# -Linux.net
KiCad netlist of a schematic drawn in Altium Designer
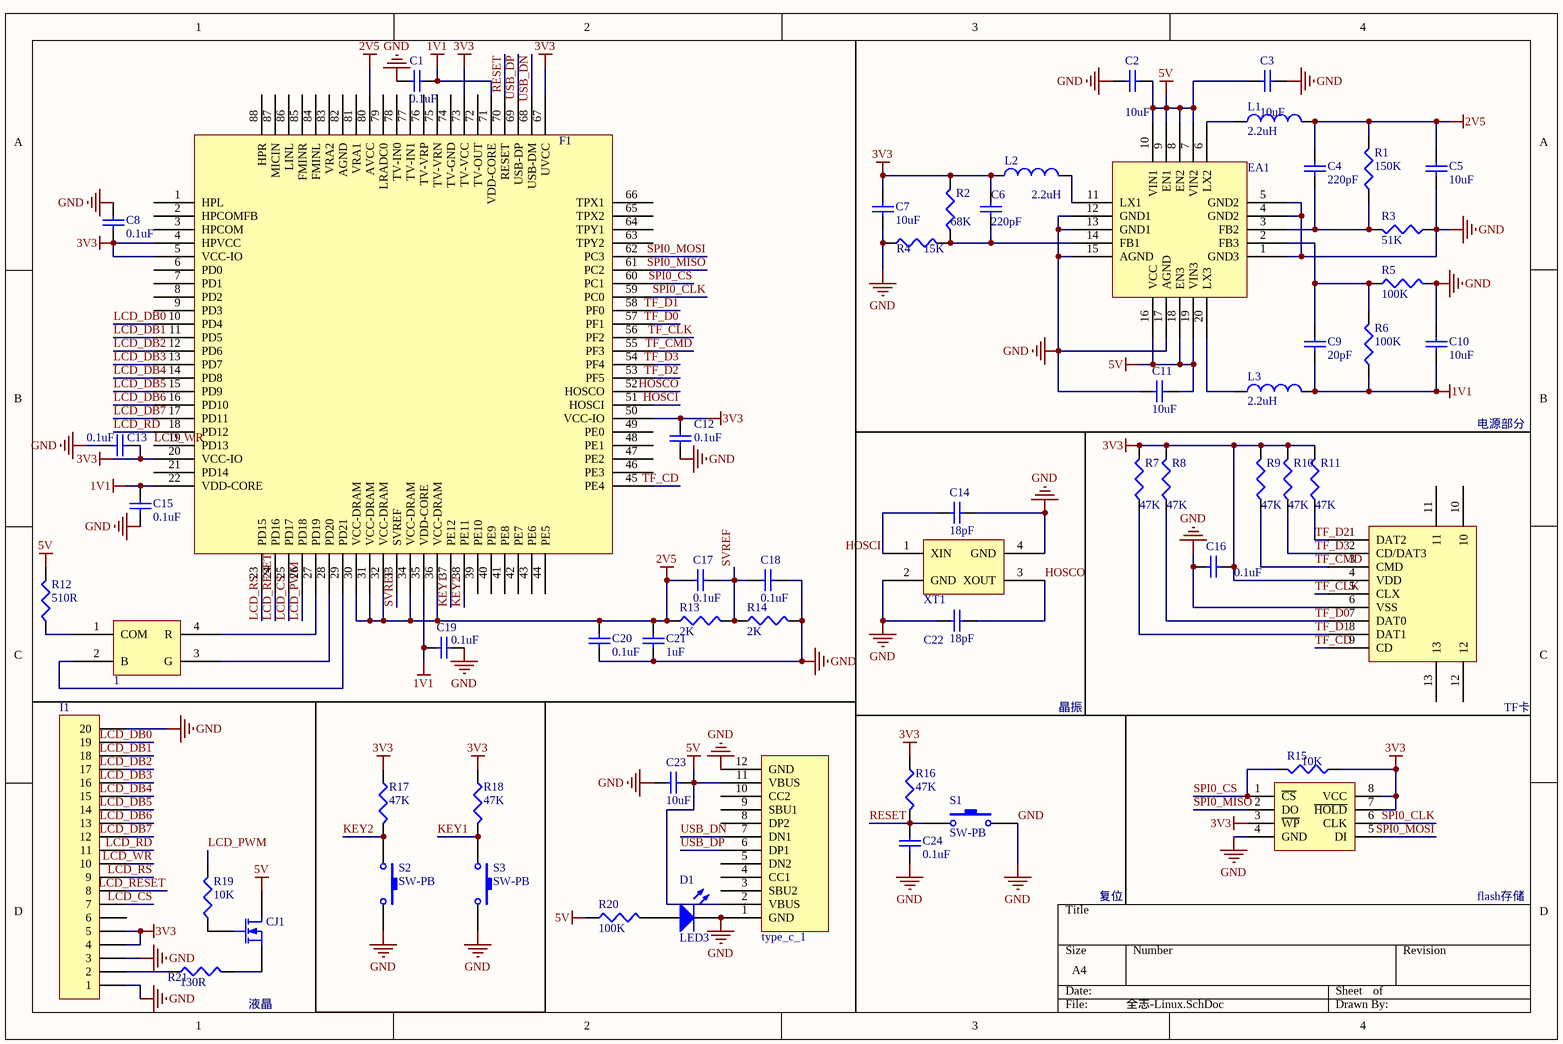
[diagram p0: 全志-Linux.SchDoc]

(export (version "E")
  (design (tool "Eeschema 10.0.6"))
  (components
    (comp (ref "*1") (value "tf卡") (footprint "tf卡座") (libsource (lib "schray_lib") (part "tf卡")))
    (comp (ref "1") (value "1615RGB") (footprint "1615RGB") (libsource (lib "schray_lib") (part "1615RGB")))
    (comp (ref "C1")
      (value "0.1uF")
      (footprint "C0402")
      (description "Capacitor (Semiconductor SIM Model)")
      (fields (field (name "Comment") "Cap Semi") (field (name "PUBLISHER") "Altium Limited"))
      (libsource (lib "Miscellaneous Devices") (part "Cap Semi"))
    )
    (comp (ref "C2")
      (value "10uF")
      (footprint "C0603")
      (description "Capacitor (Semiconductor SIM Model)")
      (fields (field (name "Comment") "Cap Semi") (field (name "PUBLISHER") "Altium Limited"))
      (libsource (lib "Miscellaneous Devices") (part "Cap Semi"))
    )
    (comp (ref "C3")
      (value "10uF")
      (footprint "C0603")
      (description "Capacitor (Semiconductor SIM Model)")
      (fields (field (name "Comment") "Cap Semi") (field (name "PUBLISHER") "Altium Limited"))
      (libsource (lib "Miscellaneous Devices") (part "Cap Semi"))
    )
    (comp (ref "C4")
      (value "220pF")
      (footprint "C0402")
      (description "Capacitor (Semiconductor SIM Model)")
      (fields (field (name "Comment") "Cap Semi") (field (name "PUBLISHER") "Altium Limited"))
      (libsource (lib "Miscellaneous Devices") (part "Cap Semi"))
    )
    (comp (ref "C5")
      (value "10uF")
      (footprint "C0603")
      (description "Capacitor (Semiconductor SIM Model)")
      (fields (field (name "Comment") "Cap Semi") (field (name "PUBLISHER") "Altium Limited"))
      (libsource (lib "Miscellaneous Devices") (part "Cap Semi"))
    )
    (comp (ref "C6")
      (value "220pF")
      (footprint "C0402")
      (description "Capacitor (Semiconductor SIM Model)")
      (fields (field (name "Comment") "Cap Semi") (field (name "PUBLISHER") "Altium Limited"))
      (libsource (lib "Miscellaneous Devices") (part "Cap Semi"))
    )
    (comp (ref "C7")
      (value "10uF")
      (footprint "C0603")
      (description "Capacitor (Semiconductor SIM Model)")
      (fields (field (name "Comment") "Cap Semi") (field (name "PUBLISHER") "Altium Limited"))
      (libsource (lib "Miscellaneous Devices") (part "Cap Semi"))
    )
    (comp (ref "C8")
      (value "0.1uF")
      (footprint "C0402")
      (description "Capacitor (Semiconductor SIM Model)")
      (fields (field (name "Comment") "Cap Semi") (field (name "PUBLISHER") "Altium Limited"))
      (libsource (lib "Miscellaneous Devices") (part "Cap Semi"))
    )
    (comp (ref "C9")
      (value "20pF")
      (footprint "C0402")
      (description "Capacitor (Semiconductor SIM Model)")
      (fields (field (name "Comment") "Cap Semi") (field (name "PUBLISHER") "Altium Limited"))
      (libsource (lib "Miscellaneous Devices") (part "Cap Semi"))
    )
    (comp (ref "C10")
      (value "10uF")
      (footprint "C0603")
      (description "Capacitor (Semiconductor SIM Model)")
      (fields (field (name "Comment") "Cap Semi") (field (name "PUBLISHER") "Altium Limited"))
      (libsource (lib "Miscellaneous Devices") (part "Cap Semi"))
    )
    (comp (ref "C11")
      (value "10uF")
      (footprint "C0603")
      (description "Capacitor (Semiconductor SIM Model)")
      (fields (field (name "Comment") "Cap Semi") (field (name "PUBLISHER") "Altium Limited"))
      (libsource (lib "Miscellaneous Devices") (part "Cap Semi"))
    )
    (comp (ref "C12")
      (value "0.1uF")
      (footprint "C0402")
      (description "Capacitor (Semiconductor SIM Model)")
      (fields (field (name "Comment") "Cap Semi") (field (name "PUBLISHER") "Altium Limited"))
      (libsource (lib "Miscellaneous Devices") (part "Cap Semi"))
    )
    (comp (ref "C13")
      (value "0.1uF")
      (footprint "C0402")
      (description "Capacitor (Semiconductor SIM Model)")
      (fields (field (name "Comment") "Cap Semi") (field (name "PUBLISHER") "Altium Limited"))
      (libsource (lib "Miscellaneous Devices") (part "Cap Semi"))
    )
    (comp (ref "C14")
      (value "18pF")
      (footprint "C0402")
      (description "Capacitor (Semiconductor SIM Model)")
      (fields (field (name "Comment") "Cap Semi") (field (name "PUBLISHER") "Altium Limited"))
      (libsource (lib "Miscellaneous Devices") (part "Cap Semi"))
    )
    (comp (ref "C15")
      (value "0.1uF")
      (footprint "C0402")
      (description "Capacitor (Semiconductor SIM Model)")
      (fields (field (name "Comment") "Cap Semi") (field (name "PUBLISHER") "Altium Limited"))
      (libsource (lib "Miscellaneous Devices") (part "Cap Semi"))
    )
    (comp (ref "C16")
      (value "0.1uF")
      (footprint "C0402")
      (description "Capacitor (Semiconductor SIM Model)")
      (fields (field (name "Comment") "Cap Semi") (field (name "PUBLISHER") "Altium Limited"))
      (libsource (lib "Miscellaneous Devices") (part "Cap Semi"))
    )
    (comp (ref "C17")
      (value "0.1uF")
      (footprint "C0402")
      (description "Capacitor (Semiconductor SIM Model)")
      (fields (field (name "Comment") "Cap Semi") (field (name "PUBLISHER") "Altium Limited"))
      (libsource (lib "Miscellaneous Devices") (part "Cap Semi"))
    )
    (comp (ref "C18")
      (value "0.1uF")
      (footprint "C0402")
      (description "Capacitor (Semiconductor SIM Model)")
      (fields (field (name "Comment") "Cap Semi") (field (name "PUBLISHER") "Altium Limited"))
      (libsource (lib "Miscellaneous Devices") (part "Cap Semi"))
    )
    (comp (ref "C19")
      (value "0.1uF")
      (footprint "C0402")
      (description "Capacitor (Semiconductor SIM Model)")
      (fields (field (name "Comment") "Cap Semi") (field (name "PUBLISHER") "Altium Limited"))
      (libsource (lib "Miscellaneous Devices") (part "Cap Semi"))
    )
    (comp (ref "C20")
      (value "0.1uF")
      (footprint "C0402")
      (description "Capacitor (Semiconductor SIM Model)")
      (fields (field (name "Comment") "Cap Semi") (field (name "PUBLISHER") "Altium Limited"))
      (libsource (lib "Miscellaneous Devices") (part "Cap Semi"))
    )
    (comp (ref "C21")
      (value "1uF")
      (footprint "C0402")
      (description "Capacitor (Semiconductor SIM Model)")
      (fields (field (name "Comment") "Cap Semi") (field (name "PUBLISHER") "Altium Limited"))
      (libsource (lib "Miscellaneous Devices") (part "Cap Semi"))
    )
    (comp (ref "C22")
      (value "18pF")
      (footprint "C0402")
      (description "Capacitor (Semiconductor SIM Model)")
      (fields (field (name "Comment") "Cap Semi") (field (name "PUBLISHER") "Altium Limited"))
      (libsource (lib "Miscellaneous Devices") (part "Cap Semi"))
    )
    (comp (ref "C23")
      (value "10uF")
      (footprint "C0603")
      (description "Capacitor (Semiconductor SIM Model)")
      (fields (field (name "Comment") "Cap Semi") (field (name "PUBLISHER") "Altium Limited"))
      (libsource (lib "Miscellaneous Devices") (part "Cap Semi"))
    )
    (comp (ref "C24")
      (value "0.1uF")
      (footprint "C0402")
      (description "Capacitor (Semiconductor SIM Model)")
      (fields (field (name "Comment") "Cap Semi") (field (name "PUBLISHER") "Altium Limited"))
      (libsource (lib "Miscellaneous Devices") (part "Cap Semi"))
    )
    (comp (ref "CJ1")
      (value "MOSFET-N")
      (footprint "SOT23")
      (description "N-Channel MOSFET")
      (fields (field (name "PUBLISHER") "Altium Limited"))
      (libsource (lib "Miscellaneous Devices") (part "MOSFET-N"))
    )
    (comp (ref "D1")
      (value "LED3")
      (footprint "LED0402 R")
      (description "Typical BLUE SiC LED")
      (fields (field (name "PUBLISHER") "Altium Limited"))
      (libsource (lib "Miscellaneous Devices") (part "LED3"))
    )
    (comp (ref "EA1") (value "EA3036") (footprint "QFN20-3mm") (libsource (lib "schray_lib") (part "EA3036")))
    (comp (ref "F1") (value "F1C100S") (footprint "QFN88") (libsource (lib "schray_lib") (part "F1C100S")))
    (comp (ref "I1")
      (value "Header 20")
      (footprint "20P液晶")
      (description "Header, 20-Pin")
      (fields (field (name "PUBLISHER") "Altium Limited"))
      (libsource (lib "Miscellaneous Connectors") (part "Header 20"))
    )
    (comp (ref "L1")
      (value "2.2uH")
      (footprint "L0805")
      (description "Inductor")
      (fields (field (name "PUBLISHER") "Altium Limited"))
      (libsource (lib "Miscellaneous Devices") (part "Inductor"))
    )
    (comp (ref "L2")
      (value "2.2uH")
      (footprint "L0805")
      (description "Inductor")
      (fields (field (name "PUBLISHER") "Altium Limited"))
      (libsource (lib "Miscellaneous Devices") (part "Inductor"))
    )
    (comp (ref "L3")
      (value "2.2uH")
      (footprint "L0805")
      (description "Inductor")
      (fields (field (name "PUBLISHER") "Altium Limited"))
      (libsource (lib "Miscellaneous Devices") (part "Inductor"))
    )
    (comp (ref "R1")
      (value "150K")
      (footprint "R0402")
      (description "Resistor")
      (fields (field (name "Comment") "Res3") (field (name "PUBLISHER") "Altium Limited"))
      (libsource (lib "Miscellaneous Devices") (part "Res3"))
    )
    (comp (ref "R2")
      (value "68K")
      (footprint "R0402")
      (description "Resistor")
      (fields (field (name "Comment") "Res3") (field (name "PUBLISHER") "Altium Limited"))
      (libsource (lib "Miscellaneous Devices") (part "Res3"))
    )
    (comp (ref "R3")
      (value "51K")
      (footprint "R0402")
      (description "Resistor")
      (fields (field (name "Comment") "Res3") (field (name "PUBLISHER") "Altium Limited"))
      (libsource (lib "Miscellaneous Devices") (part "Res3"))
    )
    (comp (ref "R4")
      (value "15K")
      (footprint "R0402")
      (description "Resistor")
      (fields (field (name "Comment") "Res3") (field (name "PUBLISHER") "Altium Limited"))
      (libsource (lib "Miscellaneous Devices") (part "Res3"))
    )
    (comp (ref "R5")
      (value "100K")
      (footprint "R0402")
      (description "Resistor")
      (fields (field (name "Comment") "Res3") (field (name "PUBLISHER") "Altium Limited"))
      (libsource (lib "Miscellaneous Devices") (part "Res3"))
    )
    (comp (ref "R6")
      (value "100K")
      (footprint "R0402")
      (description "Resistor")
      (fields (field (name "Comment") "Res3") (field (name "PUBLISHER") "Altium Limited"))
      (libsource (lib "Miscellaneous Devices") (part "Res3"))
    )
    (comp (ref "R7")
      (value "47K")
      (footprint "R0402")
      (description "Resistor")
      (fields (field (name "Comment") "Res3") (field (name "PUBLISHER") "Altium Limited"))
      (libsource (lib "Miscellaneous Devices") (part "Res3"))
    )
    (comp (ref "R8")
      (value "47K")
      (footprint "R0402")
      (description "Resistor")
      (fields (field (name "Comment") "Res3") (field (name "PUBLISHER") "Altium Limited"))
      (libsource (lib "Miscellaneous Devices") (part "Res3"))
    )
    (comp (ref "R9")
      (value "47K")
      (footprint "R0402")
      (description "Resistor")
      (fields (field (name "Comment") "Res3") (field (name "PUBLISHER") "Altium Limited"))
      (libsource (lib "Miscellaneous Devices") (part "Res3"))
    )
    (comp (ref "R10")
      (value "47K")
      (footprint "R0402")
      (description "Resistor")
      (fields (field (name "Comment") "Res3") (field (name "PUBLISHER") "Altium Limited"))
      (libsource (lib "Miscellaneous Devices") (part "Res3"))
    )
    (comp (ref "R11")
      (value "47K")
      (footprint "R0402")
      (description "Resistor")
      (fields (field (name "Comment") "Res3") (field (name "PUBLISHER") "Altium Limited"))
      (libsource (lib "Miscellaneous Devices") (part "Res3"))
    )
    (comp (ref "R12")
      (value "510R")
      (footprint "R0402")
      (description "Resistor")
      (fields (field (name "Comment") "Res3") (field (name "PUBLISHER") "Altium Limited"))
      (libsource (lib "Miscellaneous Devices") (part "Res3"))
    )
    (comp (ref "R13")
      (value "2K")
      (footprint "R0402")
      (description "Resistor")
      (fields (field (name "Comment") "Res3") (field (name "PUBLISHER") "Altium Limited"))
      (libsource (lib "Miscellaneous Devices") (part "Res3"))
    )
    (comp (ref "R14")
      (value "2K")
      (footprint "R0402")
      (description "Resistor")
      (fields (field (name "Comment") "Res3") (field (name "PUBLISHER") "Altium Limited"))
      (libsource (lib "Miscellaneous Devices") (part "Res3"))
    )
    (comp (ref "R15")
      (value "10K")
      (footprint "R0402")
      (description "Resistor")
      (fields (field (name "Comment") "Res3") (field (name "PUBLISHER") "Altium Limited"))
      (libsource (lib "Miscellaneous Devices") (part "Res3"))
    )
    (comp (ref "R16")
      (value "47K")
      (footprint "R0402")
      (description "Resistor")
      (fields (field (name "Comment") "Res3") (field (name "PUBLISHER") "Altium Limited"))
      (libsource (lib "Miscellaneous Devices") (part "Res3"))
    )
    (comp (ref "R17")
      (value "47K")
      (footprint "R0402")
      (description "Resistor")
      (fields (field (name "Comment") "Res3") (field (name "PUBLISHER") "Altium Limited"))
      (libsource (lib "Miscellaneous Devices") (part "Res3"))
    )
    (comp (ref "R18")
      (value "47K")
      (footprint "R0402")
      (description "Resistor")
      (fields (field (name "Comment") "Res3") (field (name "PUBLISHER") "Altium Limited"))
      (libsource (lib "Miscellaneous Devices") (part "Res3"))
    )
    (comp (ref "R19")
      (value "10K")
      (footprint "R0402")
      (description "Resistor")
      (fields (field (name "Comment") "Res3") (field (name "PUBLISHER") "Altium Limited"))
      (libsource (lib "Miscellaneous Devices") (part "Res3"))
    )
    (comp (ref "R20")
      (value "100K")
      (footprint "R0402")
      (description "Resistor")
      (fields (field (name "Comment") "Res3") (field (name "PUBLISHER") "Altium Limited"))
      (libsource (lib "Miscellaneous Devices") (part "Res3"))
    )
    (comp (ref "R21")
      (value "130R")
      (footprint "R0402")
      (description "Resistor")
      (fields (field (name "Comment") "Res3") (field (name "PUBLISHER") "Altium Limited"))
      (libsource (lib "Miscellaneous Devices") (part "Res3"))
    )
    (comp (ref "S1")
      (value "SW-PB")
      (footprint "3*4*2.0小龟按键")
      (description "Switch")
      (fields (field (name "PUBLISHER") "Altium Limited"))
      (libsource (lib "Miscellaneous Devices") (part "SW-PB"))
    )
    (comp (ref "S2")
      (value "SW-PB")
      (footprint "轻触按键2*4*3.5")
      (description "Switch")
      (fields (field (name "PUBLISHER") "Altium Limited"))
      (libsource (lib "Miscellaneous Devices") (part "SW-PB"))
    )
    (comp (ref "S3")
      (value "SW-PB")
      (footprint "轻触按键2*4*3.5")
      (description "Switch")
      (fields (field (name "PUBLISHER") "Altium Limited"))
      (libsource (lib "Miscellaneous Devices") (part "SW-PB"))
    )
    (comp (ref "type_c_1")
      (value "type_c_16")
      (footprint "type_c_16")
      (libsource (lib "schray_lib") (part "type_c_16"))
    )
    (comp (ref "W1")
      (value "W25Qxx")
      (footprint "SOP8")
      (description "外置Flash")
      (fields (field (name "版权归属") "源创客"))
      (libsource (lib "IC芯片") (part "W25Qxx"))
    )
    (comp (ref "XT1")
      (value "XT3225晶振")
      (footprint "XTAL-3225")
      (libsource (lib "schray_lib") (part "XT3225晶振"))
    )
  )
  (nets
    (net (code "1") (name "/HOSCI") (class "Default")
      (node (ref "C14") (pin "1") (pinfunction "1_1") (pintype "passive"))
      (node (ref "F1") (pin "51") (pinfunction "HOSCI_51") (pintype "passive"))
      (node (ref "XT1") (pin "1") (pinfunction "XIN_1") (pintype "passive"))
    )
    (net (code "2") (name "/HOSCO") (class "Default")
      (node (ref "C22") (pin "2") (pinfunction "2_2") (pintype "passive"))
      (node (ref "F1") (pin "52") (pinfunction "HOSCO_52") (pintype "passive"))
      (node (ref "XT1") (pin "3") (pinfunction "XOUT_3") (pintype "passive"))
    )
    (net (code "3") (name "/KEY1") (class "Default")
      (node (ref "F1") (pin "37") (pinfunction "PE12_37") (pintype "passive"))
      (node (ref "R18") (pin "2") (pinfunction "2_2") (pintype "passive"))
      (node (ref "S3") (pin "1") (pinfunction "1_1") (pintype "passive"))
    )
    (net (code "4") (name "/KEY2") (class "Default")
      (node (ref "F1") (pin "38") (pinfunction "PE11_38") (pintype "passive"))
      (node (ref "R17") (pin "2") (pinfunction "2_2") (pintype "passive"))
      (node (ref "S2") (pin "1") (pinfunction "1_1") (pintype "passive"))
    )
    (net (code "5") (name "/LCD_CS") (class "Default")
      (node (ref "F1") (pin "25") (pinfunction "PD17_25") (pintype "passive"))
      (node (ref "I1") (pin "7") (pinfunction "7_7") (pintype "passive"))
    )
    (net (code "6") (name "/LCD_DB0") (class "Default")
      (node (ref "F1") (pin "10") (pinfunction "PD4_10") (pintype "passive"))
      (node (ref "I1") (pin "19") (pinfunction "19_19") (pintype "passive"))
    )
    (net (code "7") (name "/LCD_DB1") (class "Default")
      (node (ref "F1") (pin "11") (pinfunction "PD5_11") (pintype "passive"))
      (node (ref "I1") (pin "18") (pinfunction "18_18") (pintype "passive"))
    )
    (net (code "8") (name "/LCD_DB2") (class "Default")
      (node (ref "F1") (pin "12") (pinfunction "PD6_12") (pintype "passive"))
      (node (ref "I1") (pin "17") (pinfunction "17_17") (pintype "passive"))
    )
    (net (code "9") (name "/LCD_DB3") (class "Default")
      (node (ref "F1") (pin "13") (pinfunction "PD7_13") (pintype "passive"))
      (node (ref "I1") (pin "16") (pinfunction "16_16") (pintype "passive"))
    )
    (net (code "10") (name "/LCD_DB4") (class "Default")
      (node (ref "F1") (pin "14") (pinfunction "PD8_14") (pintype "passive"))
      (node (ref "I1") (pin "15") (pinfunction "15_15") (pintype "passive"))
    )
    (net (code "11") (name "/LCD_DB5") (class "Default")
      (node (ref "F1") (pin "15") (pinfunction "PD9_15") (pintype "passive"))
      (node (ref "I1") (pin "14") (pinfunction "14_14") (pintype "passive"))
    )
    (net (code "12") (name "/LCD_DB6") (class "Default")
      (node (ref "F1") (pin "16") (pinfunction "PD10_16") (pintype "passive"))
      (node (ref "I1") (pin "13") (pinfunction "13_13") (pintype "passive"))
    )
    (net (code "13") (name "/LCD_DB7") (class "Default")
      (node (ref "F1") (pin "17") (pinfunction "PD11_17") (pintype "passive"))
      (node (ref "I1") (pin "12") (pinfunction "12_12") (pintype "passive"))
    )
    (net (code "14") (name "/LCD_PWM") (class "Default")
      (node (ref "F1") (pin "26") (pinfunction "PD18_26") (pintype "passive"))
      (node (ref "R19") (pin "2") (pinfunction "2_2") (pintype "passive"))
    )
    (net (code "15") (name "/LCD_RD") (class "Default")
      (node (ref "F1") (pin "18") (pinfunction "PD12_18") (pintype "passive"))
      (node (ref "I1") (pin "11") (pinfunction "11_11") (pintype "passive"))
    )
    (net (code "16") (name "/LCD_RESET") (class "Default")
      (node (ref "F1") (pin "24") (pinfunction "PD16_24") (pintype "passive"))
      (node (ref "I1") (pin "8") (pinfunction "8_8") (pintype "passive"))
    )
    (net (code "17") (name "/LCD_RS") (class "Default")
      (node (ref "F1") (pin "23") (pinfunction "PD15_23") (pintype "passive"))
      (node (ref "I1") (pin "9") (pinfunction "9_9") (pintype "passive"))
    )
    (net (code "18") (name "/LCD_WR") (class "Default")
      (node (ref "F1") (pin "19") (pinfunction "PD13_19") (pintype "passive"))
      (node (ref "I1") (pin "10") (pinfunction "10_10") (pintype "passive"))
    )
    (net (code "19") (name "/RESET") (class "Default")
      (node (ref "C24") (pin "1") (pinfunction "1_1") (pintype "passive"))
      (node (ref "F1") (pin "70") (pinfunction "RESET_70") (pintype "passive"))
      (node (ref "R16") (pin "2") (pinfunction "2_2") (pintype "passive"))
      (node (ref "S1") (pin "1") (pinfunction "1_1") (pintype "passive"))
    )
    (net (code "20") (name "/SPI0_CLK") (class "Default")
      (node (ref "F1") (pin "59") (pinfunction "PC0_59") (pintype "passive"))
      (node (ref "W1") (pin "6") (pinfunction "CLK_6") (pintype "passive"))
    )
    (net (code "21") (name "/SPI0_CS") (class "Default")
      (node (ref "F1") (pin "60") (pinfunction "PC1_60") (pintype "passive"))
      (node (ref "R15") (pin "2") (pinfunction "2_2") (pintype "passive"))
      (node (ref "W1") (pin "1") (pinfunction "~{CS}_1") (pintype "passive"))
    )
    (net (code "22") (name "/SPI0_MISO") (class "Default")
      (node (ref "F1") (pin "61") (pinfunction "PC2_61") (pintype "passive"))
      (node (ref "W1") (pin "2") (pinfunction "DO_2") (pintype "passive"))
    )
    (net (code "23") (name "/SPI0_MOSI") (class "Default")
      (node (ref "F1") (pin "62") (pinfunction "PC3_62") (pintype "passive"))
      (node (ref "W1") (pin "5") (pinfunction "DI_5") (pintype "passive"))
    )
    (net (code "24") (name "/SVREF") (class "Default")
      (node (ref "C17") (pin "1") (pinfunction "1_1") (pintype "passive"))
      (node (ref "C18") (pin "2") (pinfunction "2_2") (pintype "passive"))
      (node (ref "F1") (pin "33") (pinfunction "SVREF_33") (pintype "passive"))
      (node (ref "R13") (pin "2") (pinfunction "2_2") (pintype "passive"))
      (node (ref "R14") (pin "1") (pinfunction "1_1") (pintype "passive"))
    )
    (net (code "25") (name "/TF_CD") (class "Default")
      (node (ref "*1") (pin "9") (pinfunction "CD_9") (pintype "passive"))
      (node (ref "F1") (pin "45") (pinfunction "PE4_45") (pintype "passive"))
    )
    (net (code "26") (name "/TF_CLK") (class "Default")
      (node (ref "*1") (pin "5") (pinfunction "CLX_5") (pintype "passive"))
      (node (ref "F1") (pin "56") (pinfunction "PF2_56") (pintype "passive"))
    )
    (net (code "27") (name "/TF_CMD") (class "Default")
      (node (ref "*1") (pin "3") (pinfunction "CMD_3") (pintype "passive"))
      (node (ref "F1") (pin "55") (pinfunction "PF3_55") (pintype "passive"))
      (node (ref "R9") (pin "1") (pinfunction "1_1") (pintype "passive"))
    )
    (net (code "28") (name "/TF_D0") (class "Default")
      (node (ref "*1") (pin "7") (pinfunction "DAT0_7") (pintype "passive"))
      (node (ref "F1") (pin "57") (pinfunction "PF1_57") (pintype "passive"))
      (node (ref "R8") (pin "1") (pinfunction "1_1") (pintype "passive"))
    )
    (net (code "29") (name "/TF_D1") (class "Default")
      (node (ref "*1") (pin "8") (pinfunction "DAT1_8") (pintype "passive"))
      (node (ref "F1") (pin "58") (pinfunction "PF0_58") (pintype "passive"))
      (node (ref "R7") (pin "1") (pinfunction "1_1") (pintype "passive"))
    )
    (net (code "30") (name "/TF_D2") (class "Default")
      (node (ref "*1") (pin "1") (pinfunction "DAT2_1") (pintype "passive"))
      (node (ref "F1") (pin "53") (pinfunction "PF5_53") (pintype "passive"))
      (node (ref "R11") (pin "1") (pinfunction "1_1") (pintype "passive"))
    )
    (net (code "31") (name "/TF_D3") (class "Default")
      (node (ref "*1") (pin "2") (pinfunction "CD/DAT3_2") (pintype "passive"))
      (node (ref "F1") (pin "54") (pinfunction "PF4_54") (pintype "passive"))
      (node (ref "R10") (pin "1") (pinfunction "1_1") (pintype "passive"))
    )
    (net (code "32") (name "/USB_DN") (class "Default")
      (node (ref "F1") (pin "68") (pinfunction "USB-DM_68") (pintype "passive"))
      (node (ref "type_c_1") (pin "7") (pinfunction "DN1_7") (pintype "passive"))
    )
    (net (code "33") (name "/USB_DP") (class "Default")
      (node (ref "F1") (pin "69") (pinfunction "USB-DP_69") (pintype "passive"))
      (node (ref "type_c_1") (pin "6") (pinfunction "DP1_6") (pintype "passive"))
    )
    (net (code "34") (name "1V1") (class "Default")
      (node (ref "C1") (pin "1") (pinfunction "1_1") (pintype "passive"))
      (node (ref "C10") (pin "1") (pinfunction "1_1") (pintype "passive"))
      (node (ref "C15") (pin "1") (pinfunction "1_1") (pintype "passive"))
      (node (ref "C19") (pin "1") (pinfunction "1_1") (pintype "passive"))
      (node (ref "C9") (pin "1") (pinfunction "1_1") (pintype "passive"))
      (node (ref "F1") (pin "22") (pinfunction "VDD-CORE_22") (pintype "passive"))
      (node (ref "F1") (pin "35") (pinfunction "VDD-CORE_35") (pintype "passive"))
      (node (ref "F1") (pin "71") (pinfunction "VDD-CORE_71") (pintype "passive"))
      (node (ref "L3") (pin "2") (pinfunction "2_2") (pintype "passive"))
      (node (ref "R6") (pin "1") (pinfunction "1_1") (pintype "passive"))
    )
    (net (code "35") (name "2V5") (class "Default")
      (node (ref "C17") (pin "2") (pinfunction "2_2") (pintype "passive"))
      (node (ref "C20") (pin "1") (pinfunction "1_1") (pintype "passive"))
      (node (ref "C21") (pin "1") (pinfunction "1_1") (pintype "passive"))
      (node (ref "C4") (pin "2") (pinfunction "2_2") (pintype "passive"))
      (node (ref "C5") (pin "2") (pinfunction "2_2") (pintype "passive"))
      (node (ref "F1") (pin "30") (pinfunction "VCC-DRAM_30") (pintype "passive"))
      (node (ref "F1") (pin "31") (pinfunction "VCC-DRAM_31") (pintype "passive"))
      (node (ref "F1") (pin "32") (pinfunction "VCC-DRAM_32") (pintype "passive"))
      (node (ref "F1") (pin "34") (pinfunction "VCC-DRAM_34") (pintype "passive"))
      (node (ref "F1") (pin "36") (pinfunction "VCC-DRAM_36") (pintype "passive"))
      (node (ref "F1") (pin "80") (pinfunction "AVCC_80") (pintype "passive"))
      (node (ref "L1") (pin "2") (pinfunction "2_2") (pintype "passive"))
      (node (ref "R1") (pin "2") (pinfunction "2_2") (pintype "passive"))
      (node (ref "R13") (pin "1") (pinfunction "1_1") (pintype "passive"))
    )
    (net (code "36") (name "3V3") (class "Default")
      (node (ref "*1") (pin "4") (pinfunction "VDD_4") (pintype "passive"))
      (node (ref "C12") (pin "1") (pinfunction "1_1") (pintype "passive"))
      (node (ref "C13") (pin "1") (pinfunction "1_1") (pintype "passive"))
      (node (ref "C16") (pin "2") (pinfunction "2_2") (pintype "passive"))
      (node (ref "C6") (pin "2") (pinfunction "2_2") (pintype "passive"))
      (node (ref "C7") (pin "2") (pinfunction "2_2") (pintype "passive"))
      (node (ref "C8") (pin "1") (pinfunction "1_1") (pintype "passive"))
      (node (ref "F1") (pin "20") (pinfunction "VCC-IO_20") (pintype "passive"))
      (node (ref "F1") (pin "4") (pinfunction "HPVCC_4") (pintype "passive"))
      (node (ref "F1") (pin "5") (pinfunction "VCC-IO_5") (pintype "passive"))
      (node (ref "F1") (pin "50") (pinfunction "VCC-IO_50") (pintype "passive"))
      (node (ref "F1") (pin "67") (pinfunction "UVCC_67") (pintype "passive"))
      (node (ref "F1") (pin "73") (pinfunction "TV-VCC_73") (pintype "passive"))
      (node (ref "I1") (pin "4") (pinfunction "4_4") (pintype "passive"))
      (node (ref "I1") (pin "5") (pinfunction "5_5") (pintype "passive"))
      (node (ref "L2") (pin "1") (pinfunction "1_1") (pintype "passive"))
      (node (ref "R10") (pin "2") (pinfunction "2_2") (pintype "passive"))
      (node (ref "R11") (pin "2") (pinfunction "2_2") (pintype "passive"))
      (node (ref "R15") (pin "1") (pinfunction "1_1") (pintype "passive"))
      (node (ref "R16") (pin "1") (pinfunction "1_1") (pintype "passive"))
      (node (ref "R17") (pin "1") (pinfunction "1_1") (pintype "passive"))
      (node (ref "R18") (pin "1") (pinfunction "1_1") (pintype "passive"))
      (node (ref "R2") (pin "2") (pinfunction "2_2") (pintype "passive"))
      (node (ref "R7") (pin "2") (pinfunction "2_2") (pintype "passive"))
      (node (ref "R8") (pin "2") (pinfunction "2_2") (pintype "passive"))
      (node (ref "R9") (pin "2") (pinfunction "2_2") (pintype "passive"))
      (node (ref "W1") (pin "3") (pinfunction "~{WP}_3") (pintype "passive"))
      (node (ref "W1") (pin "7") (pinfunction "~{HOLD}_7") (pintype "passive"))
      (node (ref "W1") (pin "8") (pinfunction "VCC_8") (pintype "passive"))
    )
    (net (code "37") (name "5V") (class "Default")
      (node (ref "C11") (pin "2") (pinfunction "2_2") (pintype "passive"))
      (node (ref "C2") (pin "2") (pinfunction "2_2") (pintype "passive"))
      (node (ref "C23") (pin "1") (pinfunction "1_1") (pintype "passive"))
      (node (ref "C3") (pin "1") (pinfunction "1_1") (pintype "passive"))
      (node (ref "CJ1") (pin "1") (pinfunction "D_1") (pintype "passive"))
      (node (ref "EA1") (pin "10") (pinfunction "VIN1_10") (pintype "passive"))
      (node (ref "EA1") (pin "16") (pinfunction "VCC_16") (pintype "passive"))
      (node (ref "EA1") (pin "18") (pinfunction "EN3_18") (pintype "passive"))
      (node (ref "EA1") (pin "19") (pinfunction "VIN3_19") (pintype "passive"))
      (node (ref "EA1") (pin "7") (pinfunction "VIN2_7") (pintype "passive"))
      (node (ref "EA1") (pin "8") (pinfunction "EN2_8") (pintype "passive"))
      (node (ref "EA1") (pin "9") (pinfunction "EN1_9") (pintype "passive"))
      (node (ref "R12") (pin "2") (pinfunction "2_2") (pintype "passive"))
      (node (ref "R20") (pin "1") (pinfunction "1_1") (pintype "passive"))
      (node (ref "type_c_1") (pin "11") (pinfunction "VBUS_11") (pintype "passive"))
      (node (ref "type_c_1") (pin "2") (pinfunction "VBUS_2") (pintype "passive"))
    )
    (net (code "38") (name "GND") (class "Default")
      (node (ref "*1") (pin "6") (pinfunction "VSS_6") (pintype "passive"))
      (node (ref "C1") (pin "2") (pinfunction "2_2") (pintype "passive"))
      (node (ref "C10") (pin "2") (pinfunction "2_2") (pintype "passive"))
      (node (ref "C11") (pin "1") (pinfunction "1_1") (pintype "passive"))
      (node (ref "C12") (pin "2") (pinfunction "2_2") (pintype "passive"))
      (node (ref "C13") (pin "2") (pinfunction "2_2") (pintype "passive"))
      (node (ref "C14") (pin "2") (pinfunction "2_2") (pintype "passive"))
      (node (ref "C15") (pin "2") (pinfunction "2_2") (pintype "passive"))
      (node (ref "C16") (pin "1") (pinfunction "1_1") (pintype "passive"))
      (node (ref "C18") (pin "1") (pinfunction "1_1") (pintype "passive"))
      (node (ref "C19") (pin "2") (pinfunction "2_2") (pintype "passive"))
      (node (ref "C2") (pin "1") (pinfunction "1_1") (pintype "passive"))
      (node (ref "C20") (pin "2") (pinfunction "2_2") (pintype "passive"))
      (node (ref "C21") (pin "2") (pinfunction "2_2") (pintype "passive"))
      (node (ref "C22") (pin "1") (pinfunction "1_1") (pintype "passive"))
      (node (ref "C23") (pin "2") (pinfunction "2_2") (pintype "passive"))
      (node (ref "C24") (pin "2") (pinfunction "2_2") (pintype "passive"))
      (node (ref "C3") (pin "2") (pinfunction "2_2") (pintype "passive"))
      (node (ref "C5") (pin "1") (pinfunction "1_1") (pintype "passive"))
      (node (ref "C7") (pin "1") (pinfunction "1_1") (pintype "passive"))
      (node (ref "C8") (pin "2") (pinfunction "2_2") (pintype "passive"))
      (node (ref "D1") (pin "2") (pinfunction "K_2") (pintype "passive"))
      (node (ref "EA1") (pin "1") (pinfunction "GND3_1") (pintype "passive"))
      (node (ref "EA1") (pin "12") (pinfunction "GND1_12") (pintype "passive"))
      (node (ref "EA1") (pin "13") (pinfunction "GND1_13") (pintype "passive"))
      (node (ref "EA1") (pin "15") (pinfunction "AGND_15") (pintype "passive"))
      (node (ref "EA1") (pin "17") (pinfunction "AGND_17") (pintype "passive"))
      (node (ref "EA1") (pin "4") (pinfunction "GND2_4") (pintype "passive"))
      (node (ref "EA1") (pin "5") (pinfunction "GND2_5") (pintype "passive"))
      (node (ref "I1") (pin "1") (pinfunction "1_1") (pintype "passive"))
      (node (ref "I1") (pin "20") (pinfunction "20_20") (pintype "passive"))
      (node (ref "I1") (pin "3") (pinfunction "3_3") (pintype "passive"))
      (node (ref "R14") (pin "2") (pinfunction "2_2") (pintype "passive"))
      (node (ref "R3") (pin "1") (pinfunction "1_1") (pintype "passive"))
      (node (ref "R4") (pin "1") (pinfunction "1_1") (pintype "passive"))
      (node (ref "R5") (pin "2") (pinfunction "2_2") (pintype "passive"))
      (node (ref "S1") (pin "2") (pinfunction "2_2") (pintype "passive"))
      (node (ref "S2") (pin "2") (pinfunction "2_2") (pintype "passive"))
      (node (ref "S3") (pin "2") (pinfunction "2_2") (pintype "passive"))
      (node (ref "W1") (pin "4") (pinfunction "GND_4") (pintype "passive"))
      (node (ref "XT1") (pin "2") (pinfunction "GND_2") (pintype "passive"))
      (node (ref "XT1") (pin "4") (pinfunction "GND_4") (pintype "passive"))
      (node (ref "type_c_1") (pin "1") (pinfunction "GND_1") (pintype "passive"))
      (node (ref "type_c_1") (pin "12") (pinfunction "GND_12") (pintype "passive"))
    )
    (net (code "39") (name "Net-(1-B)") (class "Default")
      (node (ref "1") (pin "2") (pinfunction "B_2") (pintype "passive"))
      (node (ref "F1") (pin "29") (pinfunction "PD21_29") (pintype "passive"))
    )
    (net (code "40") (name "Net-(1-COM)") (class "Default")
      (node (ref "1") (pin "1") (pinfunction "COM_1") (pintype "passive"))
      (node (ref "R12") (pin "1") (pinfunction "1_1") (pintype "passive"))
    )
    (net (code "41") (name "Net-(1-G)") (class "Default")
      (node (ref "1") (pin "3") (pinfunction "G_3") (pintype "passive"))
      (node (ref "F1") (pin "28") (pinfunction "PD20_28") (pintype "passive"))
    )
    (net (code "42") (name "Net-(1-R)") (class "Default")
      (node (ref "1") (pin "4") (pinfunction "R_4") (pintype "passive"))
      (node (ref "F1") (pin "27") (pinfunction "PD19_27") (pintype "passive"))
    )
    (net (code "43") (name "Net-(CJ1-G)") (class "Default")
      (node (ref "CJ1") (pin "2") (pinfunction "G_2") (pintype "passive"))
      (node (ref "R19") (pin "1") (pinfunction "1_1") (pintype "passive"))
    )
    (net (code "44") (name "Net-(CJ1-S)") (class "Default")
      (node (ref "CJ1") (pin "3") (pinfunction "S_3") (pintype "passive"))
      (node (ref "R21") (pin "2") (pinfunction "2_2") (pintype "passive"))
    )
    (net (code "45") (name "Net-(D1-A)") (class "Default")
      (node (ref "D1") (pin "1") (pinfunction "A_1") (pintype "passive"))
      (node (ref "R20") (pin "2") (pinfunction "2_2") (pintype "passive"))
    )
    (net (code "46") (name "Net-(EA1-FB1)") (class "Default")
      (node (ref "C6") (pin "1") (pinfunction "1_1") (pintype "passive"))
      (node (ref "EA1") (pin "14") (pinfunction "FB1_14") (pintype "passive"))
      (node (ref "R2") (pin "1") (pinfunction "1_1") (pintype "passive"))
      (node (ref "R4") (pin "2") (pinfunction "2_2") (pintype "passive"))
    )
    (net (code "47") (name "Net-(EA1-FB2)") (class "Default")
      (node (ref "C4") (pin "1") (pinfunction "1_1") (pintype "passive"))
      (node (ref "EA1") (pin "3") (pinfunction "FB2_3") (pintype "passive"))
      (node (ref "R1") (pin "1") (pinfunction "1_1") (pintype "passive"))
      (node (ref "R3") (pin "2") (pinfunction "2_2") (pintype "passive"))
    )
    (net (code "48") (name "Net-(EA1-FB3)") (class "Default")
      (node (ref "C9") (pin "2") (pinfunction "2_2") (pintype "passive"))
      (node (ref "EA1") (pin "2") (pinfunction "FB3_2") (pintype "passive"))
      (node (ref "R5") (pin "1") (pinfunction "1_1") (pintype "passive"))
      (node (ref "R6") (pin "2") (pinfunction "2_2") (pintype "passive"))
    )
    (net (code "49") (name "Net-(EA1-LX1)") (class "Default")
      (node (ref "EA1") (pin "11") (pinfunction "LX1_11") (pintype "passive"))
      (node (ref "L2") (pin "2") (pinfunction "2_2") (pintype "passive"))
    )
    (net (code "50") (name "Net-(EA1-LX2)") (class "Default")
      (node (ref "EA1") (pin "6") (pinfunction "LX2_6") (pintype "passive"))
      (node (ref "L1") (pin "1") (pinfunction "1_1") (pintype "passive"))
    )
    (net (code "51") (name "Net-(EA1-LX3)") (class "Default")
      (node (ref "EA1") (pin "20") (pinfunction "LX3_20") (pintype "passive"))
      (node (ref "L3") (pin "1") (pinfunction "1_1") (pintype "passive"))
    )
    (net (code "52") (name "Net-(I1-Pad2)") (class "Default")
      (node (ref "I1") (pin "2") (pinfunction "2_2") (pintype "passive"))
      (node (ref "R21") (pin "1") (pinfunction "1_1") (pintype "passive"))
    )
    (net (code "53") (name "unconnected-(*1-Pad10)") (class "Default")
      (node (ref "*1") (pin "10") (pinfunction "10_10") (pintype "passive"))
    )
    (net (code "54") (name "unconnected-(*1-Pad11)") (class "Default")
      (node (ref "*1") (pin "11") (pinfunction "11_11") (pintype "passive"))
    )
    (net (code "55") (name "unconnected-(*1-Pad12)") (class "Default")
      (node (ref "*1") (pin "12") (pinfunction "12_12") (pintype "passive"))
    )
    (net (code "56") (name "unconnected-(*1-Pad13)") (class "Default")
      (node (ref "*1") (pin "13") (pinfunction "13_13") (pintype "passive"))
    )
    (net (code "57") (name "unconnected-(F1-AGND-Pad82)") (class "Default")
      (node (ref "F1") (pin "82") (pinfunction "AGND_82") (pintype "passive"))
    )
    (net (code "58") (name "unconnected-(F1-FMINL-Pad84)") (class "Default")
      (node (ref "F1") (pin "84") (pinfunction "FMINL_84") (pintype "passive"))
    )
    (net (code "59") (name "unconnected-(F1-FMINR-Pad85)") (class "Default")
      (node (ref "F1") (pin "85") (pinfunction "FMINR_85") (pintype "passive"))
    )
    (net (code "60") (name "unconnected-(F1-HPCOM-Pad3)") (class "Default")
      (node (ref "F1") (pin "3") (pinfunction "HPCOM_3") (pintype "passive"))
    )
    (net (code "61") (name "unconnected-(F1-HPCOMFB-Pad2)") (class "Default")
      (node (ref "F1") (pin "2") (pinfunction "HPCOMFB_2") (pintype "passive"))
    )
    (net (code "62") (name "unconnected-(F1-HPL-Pad1)") (class "Default")
      (node (ref "F1") (pin "1") (pinfunction "HPL_1") (pintype "passive"))
    )
    (net (code "63") (name "unconnected-(F1-HPR-Pad88)") (class "Default")
      (node (ref "F1") (pin "88") (pinfunction "HPR_88") (pintype "passive"))
    )
    (net (code "64") (name "unconnected-(F1-LINL-Pad86)") (class "Default")
      (node (ref "F1") (pin "86") (pinfunction "LINL_86") (pintype "passive"))
    )
    (net (code "65") (name "unconnected-(F1-LRADC0-Pad79)") (class "Default")
      (node (ref "F1") (pin "79") (pinfunction "LRADC0_79") (pintype "passive"))
    )
    (net (code "66") (name "unconnected-(F1-MICIN-Pad87)") (class "Default")
      (node (ref "F1") (pin "87") (pinfunction "MICIN_87") (pintype "passive"))
    )
    (net (code "67") (name "unconnected-(F1-PD0-Pad6)") (class "Default")
      (node (ref "F1") (pin "6") (pinfunction "PD0_6") (pintype "passive"))
    )
    (net (code "68") (name "unconnected-(F1-PD1-Pad7)") (class "Default")
      (node (ref "F1") (pin "7") (pinfunction "PD1_7") (pintype "passive"))
    )
    (net (code "69") (name "unconnected-(F1-PD2-Pad8)") (class "Default")
      (node (ref "F1") (pin "8") (pinfunction "PD2_8") (pintype "passive"))
    )
    (net (code "70") (name "unconnected-(F1-PD3-Pad9)") (class "Default")
      (node (ref "F1") (pin "9") (pinfunction "PD3_9") (pintype "passive"))
    )
    (net (code "71") (name "unconnected-(F1-PD14-Pad21)") (class "Default")
      (node (ref "F1") (pin "21") (pinfunction "PD14_21") (pintype "passive"))
    )
    (net (code "72") (name "unconnected-(F1-PE0-Pad49)") (class "Default")
      (node (ref "F1") (pin "49") (pinfunction "PE0_49") (pintype "passive"))
    )
    (net (code "73") (name "unconnected-(F1-PE1-Pad48)") (class "Default")
      (node (ref "F1") (pin "48") (pinfunction "PE1_48") (pintype "passive"))
    )
    (net (code "74") (name "unconnected-(F1-PE2-Pad47)") (class "Default")
      (node (ref "F1") (pin "47") (pinfunction "PE2_47") (pintype "passive"))
    )
    (net (code "75") (name "unconnected-(F1-PE3-Pad46)") (class "Default")
      (node (ref "F1") (pin "46") (pinfunction "PE3_46") (pintype "passive"))
    )
    (net (code "76") (name "unconnected-(F1-PE5-Pad44)") (class "Default")
      (node (ref "F1") (pin "44") (pinfunction "PE5_44") (pintype "passive"))
    )
    (net (code "77") (name "unconnected-(F1-PE6-Pad43)") (class "Default")
      (node (ref "F1") (pin "43") (pinfunction "PE6_43") (pintype "passive"))
    )
    (net (code "78") (name "unconnected-(F1-PE7-Pad42)") (class "Default")
      (node (ref "F1") (pin "42") (pinfunction "PE7_42") (pintype "passive"))
    )
    (net (code "79") (name "unconnected-(F1-PE8-Pad41)") (class "Default")
      (node (ref "F1") (pin "41") (pinfunction "PE8_41") (pintype "passive"))
    )
    (net (code "80") (name "unconnected-(F1-PE9-Pad40)") (class "Default")
      (node (ref "F1") (pin "40") (pinfunction "PE9_40") (pintype "passive"))
    )
    (net (code "81") (name "unconnected-(F1-PE10-Pad39)") (class "Default")
      (node (ref "F1") (pin "39") (pinfunction "PE10_39") (pintype "passive"))
    )
    (net (code "82") (name "unconnected-(F1-TPX1-Pad66)") (class "Default")
      (node (ref "F1") (pin "66") (pinfunction "TPX1_66") (pintype "passive"))
    )
    (net (code "83") (name "unconnected-(F1-TPX2-Pad65)") (class "Default")
      (node (ref "F1") (pin "65") (pinfunction "TPX2_65") (pintype "passive"))
    )
    (net (code "84") (name "unconnected-(F1-TPY1-Pad64)") (class "Default")
      (node (ref "F1") (pin "64") (pinfunction "TPY1_64") (pintype "passive"))
    )
    (net (code "85") (name "unconnected-(F1-TPY2-Pad63)") (class "Default")
      (node (ref "F1") (pin "63") (pinfunction "TPY2_63") (pintype "passive"))
    )
    (net (code "86") (name "unconnected-(F1-TV-GND-Pad74)") (class "Default")
      (node (ref "F1") (pin "74") (pinfunction "TV-GND_74") (pintype "passive"))
    )
    (net (code "87") (name "unconnected-(F1-TV-IN0-Pad78)") (class "Default")
      (node (ref "F1") (pin "78") (pinfunction "TV-IN0_78") (pintype "passive"))
    )
    (net (code "88") (name "unconnected-(F1-TV-IN1-Pad77)") (class "Default")
      (node (ref "F1") (pin "77") (pinfunction "TV-IN1_77") (pintype "passive"))
    )
    (net (code "89") (name "unconnected-(F1-TV-OUT-Pad72)") (class "Default")
      (node (ref "F1") (pin "72") (pinfunction "TV-OUT_72") (pintype "passive"))
    )
    (net (code "90") (name "unconnected-(F1-TV-VRN-Pad75)") (class "Default")
      (node (ref "F1") (pin "75") (pinfunction "TV-VRN_75") (pintype "passive"))
    )
    (net (code "91") (name "unconnected-(F1-TV-VRP-Pad76)") (class "Default")
      (node (ref "F1") (pin "76") (pinfunction "TV-VRP_76") (pintype "passive"))
    )
    (net (code "92") (name "unconnected-(F1-VRA1-Pad81)") (class "Default")
      (node (ref "F1") (pin "81") (pinfunction "VRA1_81") (pintype "passive"))
    )
    (net (code "93") (name "unconnected-(F1-VRA2-Pad83)") (class "Default")
      (node (ref "F1") (pin "83") (pinfunction "VRA2_83") (pintype "passive"))
    )
    (net (code "94") (name "unconnected-(I1-Pad6)") (class "Default")
      (node (ref "I1") (pin "6") (pinfunction "6_6") (pintype "passive"))
    )
    (net (code "95") (name "unconnected-(type_c_1-CC1-Pad4)") (class "Default")
      (node (ref "type_c_1") (pin "4") (pinfunction "CC1_4") (pintype "passive"))
    )
    (net (code "96") (name "unconnected-(type_c_1-CC2-Pad10)") (class "Default")
      (node (ref "type_c_1") (pin "10") (pinfunction "CC2_10") (pintype "passive"))
    )
    (net (code "97") (name "unconnected-(type_c_1-DN2-Pad5)") (class "Default")
      (node (ref "type_c_1") (pin "5") (pinfunction "DN2_5") (pintype "passive"))
    )
    (net (code "98") (name "unconnected-(type_c_1-DP2-Pad8)") (class "Default")
      (node (ref "type_c_1") (pin "8") (pinfunction "DP2_8") (pintype "passive"))
    )
    (net (code "99") (name "unconnected-(type_c_1-SBU1-Pad9)") (class "Default")
      (node (ref "type_c_1") (pin "9") (pinfunction "SBU1_9") (pintype "passive"))
    )
    (net (code "100") (name "unconnected-(type_c_1-SBU2-Pad3)") (class "Default")
      (node (ref "type_c_1") (pin "3") (pinfunction "SBU2_3") (pintype "passive"))
    )
  )
)
